# mytracer.net
KiCad netlist of a schematic drawn in EAGLE
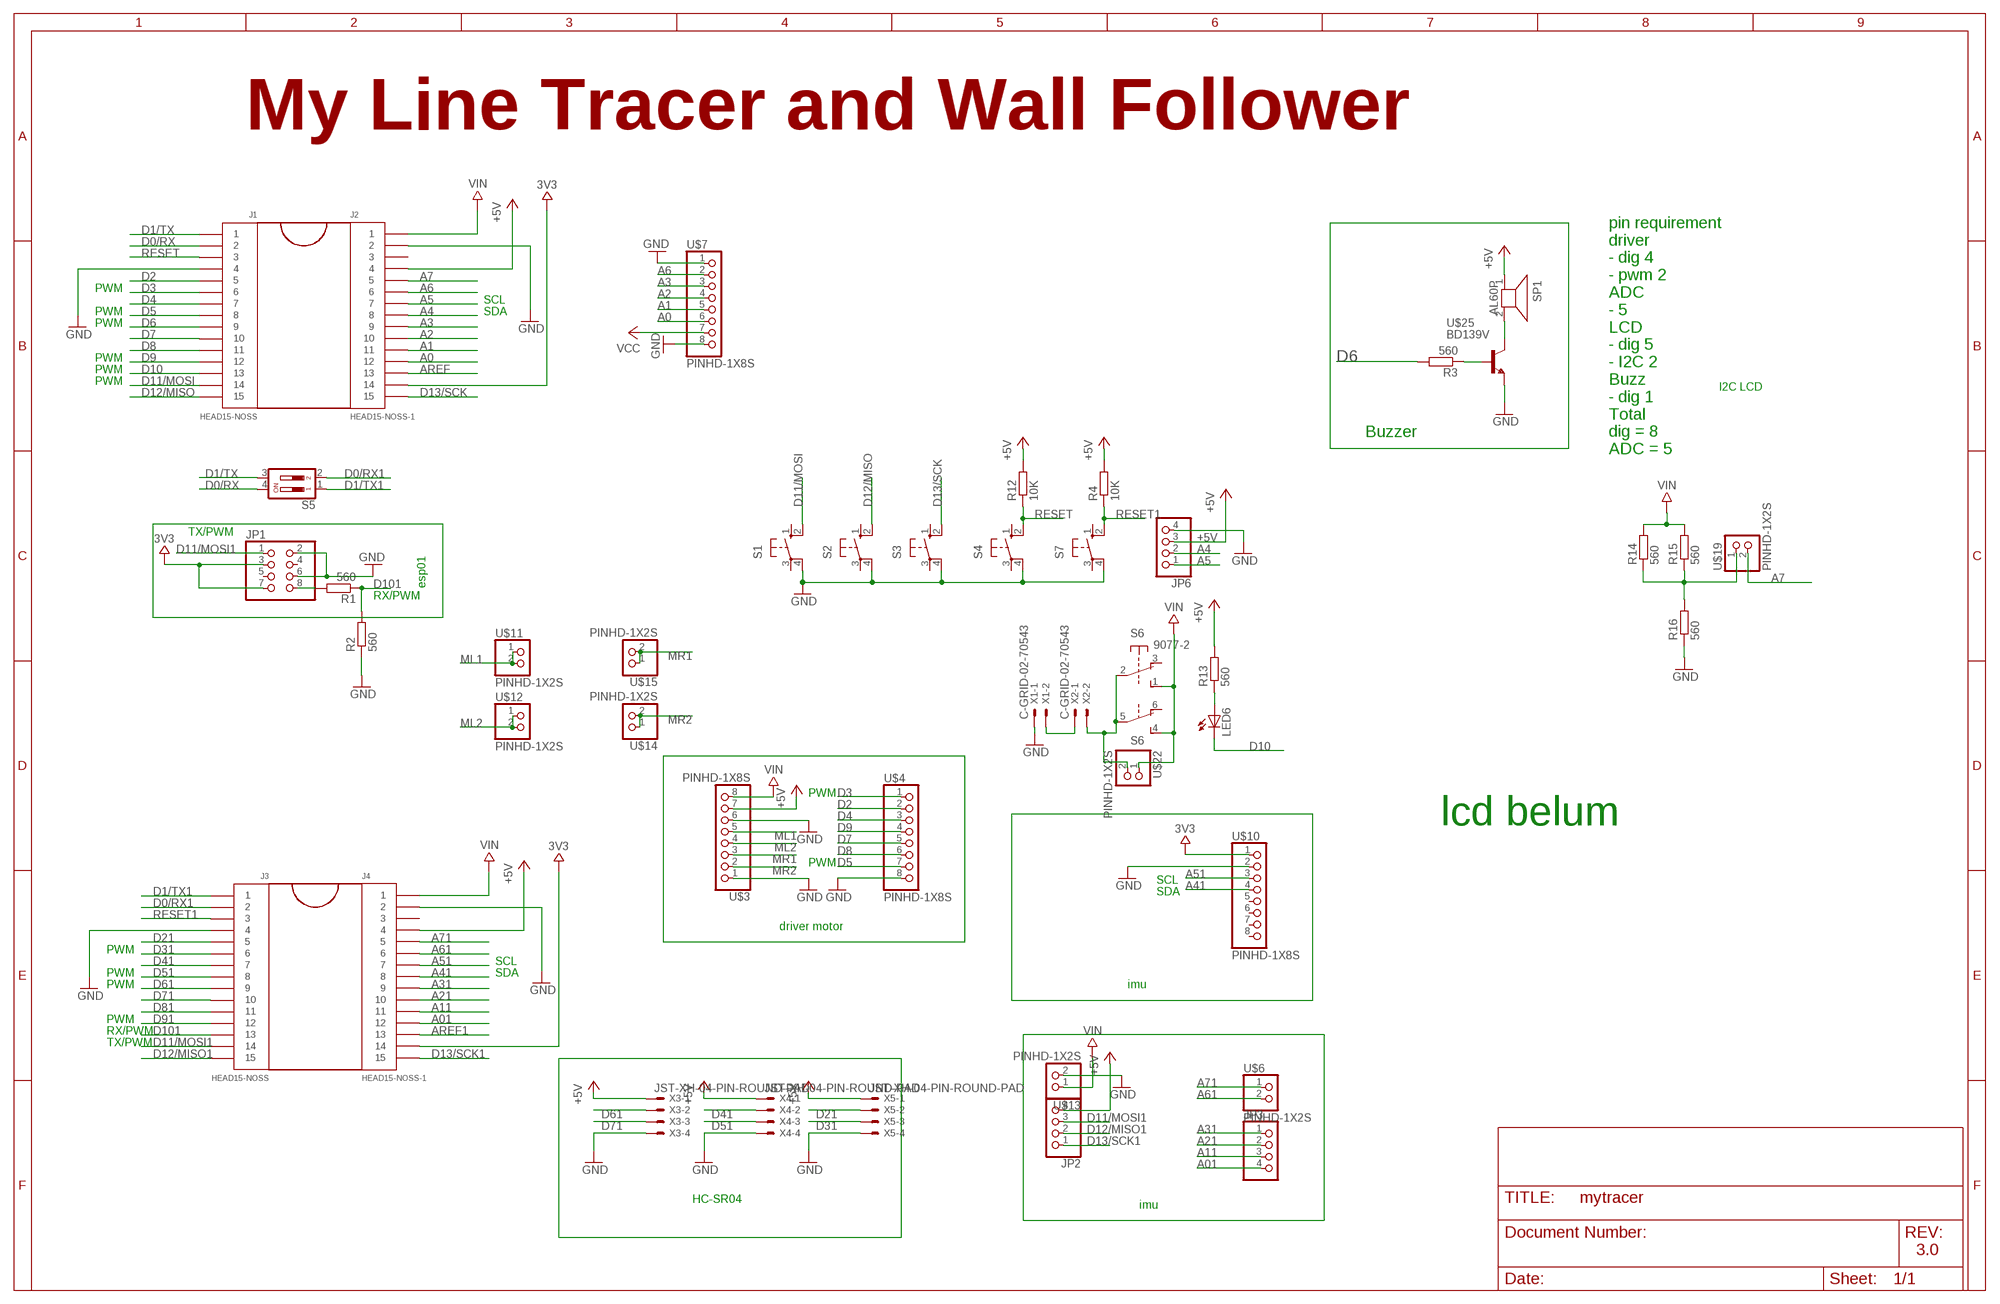
[diagram p0: schematic, sheet 1]

(export (version "E")
  (design (tool "Eeschema 10.0.6"))
  (components
    (comp (ref "J1")
      (value "HEAD15-NOSS")
      (footprint "eagle-import:HEAD15-NOSS")
      (libsource (lib "eagle-import") (part "HEAD15-NOSS"))
    )
    (comp (ref "J2")
      (value "HEAD15-NOSS-1")
      (footprint "eagle-import:HEAD15-NOSS-1")
      (libsource (lib "eagle-import") (part "HEAD15-NOSS-1"))
    )
    (comp (ref "J3")
      (value "HEAD15-NOSS")
      (footprint "eagle-import:HEAD15-NOSS")
      (libsource (lib "eagle-import") (part "HEAD15-NOSS"))
    )
    (comp (ref "J4")
      (value "HEAD15-NOSS-1")
      (footprint "eagle-import:HEAD15-NOSS-1")
      (libsource (lib "eagle-import") (part "HEAD15-NOSS-1"))
    )
    (comp (ref "JP1")
      (value "PINHD-2X4")
      (footprint "eagle-import:2X04")
      (libsource (lib "eagle-import") (part "PINHD-2X4"))
    )
    (comp (ref "JP2")
      (value "PINHD-1X4")
      (footprint "eagle-import:1X04")
      (libsource (lib "eagle-import") (part "PINHD-1X4"))
    )
    (comp (ref "JP3")
      (value "PINHD-1X4")
      (footprint "eagle-import:1X04")
      (libsource (lib "eagle-import") (part "PINHD-1X4"))
    )
    (comp (ref "JP6")
      (value "PINHD-1X4")
      (footprint "eagle-import:1X04")
      (libsource (lib "eagle-import") (part "PINHD-1X4"))
    )
    (comp (ref "LED6")
      (value "LED3MM")
      (footprint "eagle-import:LED3MM")
      (libsource (lib "eagle-import") (part "LED3MM"))
    )
    (comp (ref "R1")
      (value "560")
      (footprint "eagle-import:M1206")
      (libsource (lib "eagle-import") (part "R-EU_M1206"))
    )
    (comp (ref "R2")
      (value "560")
      (footprint "eagle-import:M1206")
      (libsource (lib "eagle-import") (part "R-EU_M1206"))
    )
    (comp (ref "R3")
      (value "560")
      (footprint "eagle-import:M1206")
      (libsource (lib "eagle-import") (part "R-EU_M1206"))
    )
    (comp (ref "R4")
      (value "10K")
      (footprint "eagle-import:M1206")
      (libsource (lib "eagle-import") (part "R-EU_M1206"))
    )
    (comp (ref "R12")
      (value "10K")
      (footprint "eagle-import:M1206")
      (libsource (lib "eagle-import") (part "R-EU_M1206"))
    )
    (comp (ref "R13")
      (value "560")
      (footprint "eagle-import:M1206")
      (libsource (lib "eagle-import") (part "R-EU_M1206"))
    )
    (comp (ref "R14")
      (value "560")
      (footprint "eagle-import:M1206")
      (libsource (lib "eagle-import") (part "R-EU_M1206"))
    )
    (comp (ref "R15")
      (value "560")
      (footprint "eagle-import:M1206")
      (libsource (lib "eagle-import") (part "R-EU_M1206"))
    )
    (comp (ref "R16")
      (value "560")
      (footprint "eagle-import:M1206")
      (libsource (lib "eagle-import") (part "R-EU_M1206"))
    )
    (comp (ref "S1")
      (value "10-XX")
      (footprint "eagle-import:B3F-10XX")
      (fields (field (name "MPN") "B3F-1000"))
      (libsource (lib "eagle-import") (part "10-XX"))
    )
    (comp (ref "S2")
      (value "10-XX")
      (footprint "eagle-import:B3F-10XX")
      (fields (field (name "MPN") "B3F-1000"))
      (libsource (lib "eagle-import") (part "10-XX"))
    )
    (comp (ref "S3")
      (value "10-XX")
      (footprint "eagle-import:B3F-10XX")
      (fields (field (name "MPN") "B3F-1000"))
      (libsource (lib "eagle-import") (part "10-XX"))
    )
    (comp (ref "S4")
      (value "10-XX")
      (footprint "eagle-import:B3F-10XX")
      (fields (field (name "MPN") "B3F-1000"))
      (libsource (lib "eagle-import") (part "10-XX"))
    )
    (comp (ref "S5")
      (value "DIP02YL")
      (footprint "eagle-import:DIP02YL")
      (libsource (lib "eagle-import") (part "DIP02YL"))
    )
    (comp (ref "S6")
      (value "9077-2")
      (footprint "eagle-import:9077-2")
      (libsource (lib "eagle-import") (part "9077-2"))
    )
    (comp (ref "S7")
      (value "10-XX")
      (footprint "eagle-import:B3F-10XX")
      (fields (field (name "MPN") "B3F-1000"))
      (libsource (lib "eagle-import") (part "10-XX"))
    )
    (comp (ref "SP1")
      (value "AL60P")
      (footprint "eagle-import:AL60P")
      (libsource (lib "eagle-import") (part "AL60P"))
    )
    (comp (ref "U$3")
      (value "PINHD-1X8S")
      (footprint "eagle-import:1X08S")
      (libsource (lib "eagle-import") (part "PINHD-1X8S"))
    )
    (comp (ref "U$4")
      (value "PINHD-1X8S")
      (footprint "eagle-import:1X08S")
      (libsource (lib "eagle-import") (part "PINHD-1X8S"))
    )
    (comp (ref "U$6")
      (value "PINHD-1X2S")
      (footprint "eagle-import:1X02S")
      (libsource (lib "eagle-import") (part "PINHD-1X2S"))
    )
    (comp (ref "U$7")
      (value "PINHD-1X8S")
      (footprint "eagle-import:1X08S")
      (libsource (lib "eagle-import") (part "PINHD-1X8S"))
    )
    (comp (ref "U$10")
      (value "PINHD-1X8S")
      (footprint "eagle-import:1X08S")
      (libsource (lib "eagle-import") (part "PINHD-1X8S"))
    )
    (comp (ref "U$11")
      (value "PINHD-1X2S")
      (footprint "eagle-import:1X02S")
      (libsource (lib "eagle-import") (part "PINHD-1X2S"))
    )
    (comp (ref "U$12")
      (value "PINHD-1X2S")
      (footprint "eagle-import:1X02S")
      (libsource (lib "eagle-import") (part "PINHD-1X2S"))
    )
    (comp (ref "U$13")
      (value "PINHD-1X2S")
      (footprint "eagle-import:1X02S")
      (libsource (lib "eagle-import") (part "PINHD-1X2S"))
    )
    (comp (ref "U$14")
      (value "PINHD-1X2S")
      (footprint "eagle-import:1X02S")
      (libsource (lib "eagle-import") (part "PINHD-1X2S"))
    )
    (comp (ref "U$15")
      (value "PINHD-1X2S")
      (footprint "eagle-import:1X02S")
      (libsource (lib "eagle-import") (part "PINHD-1X2S"))
    )
    (comp (ref "U$19")
      (value "PINHD-1X2S")
      (footprint "eagle-import:1X02S")
      (libsource (lib "eagle-import") (part "PINHD-1X2S"))
    )
    (comp (ref "U$22")
      (value "PINHD-1X2S")
      (footprint "eagle-import:1X02S")
      (libsource (lib "eagle-import") (part "PINHD-1X2S"))
    )
    (comp (ref "U$25")
      (value "BD139V")
      (footprint "eagle-import:TO126V")
      (libsource (lib "eagle-import") (part "BD139V"))
    )
    (comp (ref "X1")
      (value "C-GRID-02-70543")
      (footprint "eagle-import:70543-02")
      (libsource (lib "eagle-import") (part "C-GRID-02-70543"))
    )
    (comp (ref "X2")
      (value "C-GRID-02-70543")
      (footprint "eagle-import:70543-02")
      (libsource (lib "eagle-import") (part "C-GRID-02-70543"))
    )
    (comp (ref "X3")
      (value "JST-XH-04-PIN-ROUND-PAD")
      (footprint "eagle-import:JST-XH-04-PACKAGE-ROUND-PAD")
      (libsource (lib "eagle-import") (part "JST-XH-04-PIN-ROUND-PAD"))
    )
    (comp (ref "X4")
      (value "JST-XH-04-PIN-ROUND-PAD")
      (footprint "eagle-import:JST-XH-04-PACKAGE-ROUND-PAD")
      (libsource (lib "eagle-import") (part "JST-XH-04-PIN-ROUND-PAD"))
    )
    (comp (ref "X5")
      (value "JST-XH-04-PIN-ROUND-PAD")
      (footprint "eagle-import:JST-XH-04-PACKAGE-ROUND-PAD")
      (libsource (lib "eagle-import") (part "JST-XH-04-PIN-ROUND-PAD"))
    )
  )
  (nets
    (net (code "1") (name "+5V") (class "Default")
      (node (ref "J2") (pin "4") (pinfunction "4_4") (pintype "passive"))
      (node (ref "J4") (pin "4") (pinfunction "4_4") (pintype "passive"))
      (node (ref "JP2") (pin "4") (pinfunction "4_4") (pintype "passive"))
      (node (ref "JP6") (pin "3") (pinfunction "3_3") (pintype "passive"))
      (node (ref "R12") (pin "2") (pinfunction "2_2") (pintype "passive"))
      (node (ref "R13") (pin "2") (pinfunction "2_2") (pintype "passive"))
      (node (ref "R4") (pin "2") (pinfunction "2_2") (pintype "passive"))
      (node (ref "SP1") (pin "1") (pinfunction "1_1") (pintype "passive"))
      (node (ref "U$3") (pin "7") (pinfunction "7_7") (pintype "passive"))
      (node (ref "X3") (pin "1") (pinfunction "S_1") (pintype "passive"))
      (node (ref "X4") (pin "1") (pinfunction "S_1") (pintype "passive"))
      (node (ref "X5") (pin "1") (pinfunction "S_1") (pintype "passive"))
    )
    (net (code "2") (name "/A0") (class "Default")
      (node (ref "J2") (pin "12") (pinfunction "12_12") (pintype "passive"))
      (node (ref "U$7") (pin "6") (pinfunction "6_6") (pintype "passive"))
    )
    (net (code "3") (name "/A01") (class "Default")
      (node (ref "J4") (pin "12") (pinfunction "12_12") (pintype "passive"))
      (node (ref "JP3") (pin "4") (pinfunction "4_4") (pintype "passive"))
    )
    (net (code "4") (name "/A1") (class "Default")
      (node (ref "J2") (pin "11") (pinfunction "11_11") (pintype "passive"))
      (node (ref "U$7") (pin "5") (pinfunction "5_5") (pintype "passive"))
    )
    (net (code "5") (name "/A2") (class "Default")
      (node (ref "J2") (pin "10") (pinfunction "10_10") (pintype "passive"))
      (node (ref "U$7") (pin "4") (pinfunction "4_4") (pintype "passive"))
    )
    (net (code "6") (name "/A3") (class "Default")
      (node (ref "J2") (pin "9") (pinfunction "9_9") (pintype "passive"))
      (node (ref "U$7") (pin "3") (pinfunction "3_3") (pintype "passive"))
    )
    (net (code "7") (name "/A4") (class "Default")
      (node (ref "J2") (pin "8") (pinfunction "8_8") (pintype "passive"))
      (node (ref "JP6") (pin "2") (pinfunction "2_2") (pintype "passive"))
    )
    (net (code "8") (name "/A5") (class "Default")
      (node (ref "J2") (pin "7") (pinfunction "7_7") (pintype "passive"))
      (node (ref "JP6") (pin "1") (pinfunction "1_1") (pintype "passive"))
    )
    (net (code "9") (name "/A6") (class "Default")
      (node (ref "J2") (pin "6") (pinfunction "6_6") (pintype "passive"))
      (node (ref "U$7") (pin "2") (pinfunction "2_2") (pintype "passive"))
    )
    (net (code "10") (name "/A7") (class "Default")
      (node (ref "J2") (pin "5") (pinfunction "5_5") (pintype "passive"))
      (node (ref "U$19") (pin "2") (pinfunction "2_2") (pintype "passive"))
    )
    (net (code "11") (name "/A11") (class "Default")
      (node (ref "J4") (pin "11") (pinfunction "11_11") (pintype "passive"))
      (node (ref "JP3") (pin "3") (pinfunction "3_3") (pintype "passive"))
    )
    (net (code "12") (name "/A21") (class "Default")
      (node (ref "J4") (pin "10") (pinfunction "10_10") (pintype "passive"))
      (node (ref "JP3") (pin "2") (pinfunction "2_2") (pintype "passive"))
    )
    (net (code "13") (name "/A31") (class "Default")
      (node (ref "J4") (pin "9") (pinfunction "9_9") (pintype "passive"))
      (node (ref "JP3") (pin "1") (pinfunction "1_1") (pintype "passive"))
    )
    (net (code "14") (name "/A41") (class "Default")
      (node (ref "J4") (pin "8") (pinfunction "8_8") (pintype "passive"))
      (node (ref "U$10") (pin "4") (pinfunction "4_4") (pintype "passive"))
    )
    (net (code "15") (name "/A51") (class "Default")
      (node (ref "J4") (pin "7") (pinfunction "7_7") (pintype "passive"))
      (node (ref "U$10") (pin "3") (pinfunction "3_3") (pintype "passive"))
    )
    (net (code "16") (name "/A61") (class "Default")
      (node (ref "J4") (pin "6") (pinfunction "6_6") (pintype "passive"))
      (node (ref "U$6") (pin "2") (pinfunction "2_2") (pintype "passive"))
    )
    (net (code "17") (name "/A71") (class "Default")
      (node (ref "J4") (pin "5") (pinfunction "5_5") (pintype "passive"))
      (node (ref "U$6") (pin "1") (pinfunction "1_1") (pintype "passive"))
    )
    (net (code "18") (name "/AREF") (class "Default")
      (node (ref "J2") (pin "13") (pinfunction "13_13") (pintype "passive"))
    )
    (net (code "19") (name "/AREF1") (class "Default")
      (node (ref "J4") (pin "13") (pinfunction "13_13") (pintype "passive"))
    )
    (net (code "20") (name "/D0{slash}RX") (class "Default")
      (node (ref "J1") (pin "2") (pinfunction "2_2") (pintype "passive"))
      (node (ref "S5") (pin "4") (pinfunction "4_4") (pintype "passive"))
    )
    (net (code "21") (name "/D0{slash}RX1") (class "Default")
      (node (ref "J3") (pin "2") (pinfunction "2_2") (pintype "passive"))
      (node (ref "S5") (pin "2") (pinfunction "2_2") (pintype "passive"))
    )
    (net (code "22") (name "/D1{slash}TX") (class "Default")
      (node (ref "J1") (pin "1") (pinfunction "1_1") (pintype "passive"))
      (node (ref "S5") (pin "3") (pinfunction "3_3") (pintype "passive"))
    )
    (net (code "23") (name "/D1{slash}TX1") (class "Default")
      (node (ref "J3") (pin "1") (pinfunction "1_1") (pintype "passive"))
      (node (ref "S5") (pin "1") (pinfunction "1_1") (pintype "passive"))
    )
    (net (code "24") (name "/D2") (class "Default")
      (node (ref "J1") (pin "5") (pinfunction "5_5") (pintype "passive"))
      (node (ref "U$4") (pin "2") (pinfunction "2_2") (pintype "passive"))
    )
    (net (code "25") (name "/D3") (class "Default")
      (node (ref "J1") (pin "6") (pinfunction "6_6") (pintype "passive"))
      (node (ref "U$4") (pin "1") (pinfunction "1_1") (pintype "passive"))
    )
    (net (code "26") (name "/D4") (class "Default")
      (node (ref "J1") (pin "7") (pinfunction "7_7") (pintype "passive"))
      (node (ref "U$4") (pin "3") (pinfunction "3_3") (pintype "passive"))
    )
    (net (code "27") (name "/D5") (class "Default")
      (node (ref "J1") (pin "8") (pinfunction "8_8") (pintype "passive"))
      (node (ref "U$4") (pin "7") (pinfunction "7_7") (pintype "passive"))
    )
    (net (code "28") (name "/D6") (class "Default")
      (node (ref "J1") (pin "9") (pinfunction "9_9") (pintype "passive"))
      (node (ref "R3") (pin "2") (pinfunction "2_2") (pintype "passive"))
    )
    (net (code "29") (name "/D7") (class "Default")
      (node (ref "J1") (pin "10") (pinfunction "10_10") (pintype "passive"))
      (node (ref "U$4") (pin "5") (pinfunction "5_5") (pintype "passive"))
    )
    (net (code "30") (name "/D8") (class "Default")
      (node (ref "J1") (pin "11") (pinfunction "11_11") (pintype "passive"))
      (node (ref "U$4") (pin "6") (pinfunction "6_6") (pintype "passive"))
    )
    (net (code "31") (name "/D9") (class "Default")
      (node (ref "J1") (pin "12") (pinfunction "12_12") (pintype "passive"))
      (node (ref "U$4") (pin "4") (pinfunction "4_4") (pintype "passive"))
    )
    (net (code "32") (name "/D10") (class "Default")
      (node (ref "J1") (pin "13") (pinfunction "13_13") (pintype "passive"))
      (node (ref "LED6") (pin "K") (pinfunction "C_K") (pintype "passive"))
    )
    (net (code "33") (name "/D11{slash}MOSI") (class "Default")
      (node (ref "J1") (pin "14") (pinfunction "14_14") (pintype "passive"))
      (node (ref "S1") (pin "2") (pinfunction "S1_2") (pintype "passive"))
    )
    (net (code "34") (name "/D11{slash}MOSI1") (class "Default")
      (node (ref "J3") (pin "14") (pinfunction "14_14") (pintype "passive"))
      (node (ref "JP1") (pin "1") (pinfunction "1_1") (pintype "passive"))
      (node (ref "JP2") (pin "3") (pinfunction "3_3") (pintype "passive"))
    )
    (net (code "35") (name "/D12{slash}MISO") (class "Default")
      (node (ref "J1") (pin "15") (pinfunction "15_15") (pintype "passive"))
      (node (ref "S2") (pin "2") (pinfunction "S1_2") (pintype "passive"))
    )
    (net (code "36") (name "/D12{slash}MISO1") (class "Default")
      (node (ref "J3") (pin "15") (pinfunction "15_15") (pintype "passive"))
      (node (ref "JP2") (pin "2") (pinfunction "2_2") (pintype "passive"))
    )
    (net (code "37") (name "/D13{slash}SCK") (class "Default")
      (node (ref "J2") (pin "15") (pinfunction "15_15") (pintype "passive"))
      (node (ref "S3") (pin "2") (pinfunction "S1_2") (pintype "passive"))
    )
    (net (code "38") (name "/D13{slash}SCK1") (class "Default")
      (node (ref "J4") (pin "15") (pinfunction "15_15") (pintype "passive"))
      (node (ref "JP2") (pin "1") (pinfunction "1_1") (pintype "passive"))
    )
    (net (code "39") (name "/D21") (class "Default")
      (node (ref "J3") (pin "5") (pinfunction "5_5") (pintype "passive"))
      (node (ref "X5") (pin "2") (pinfunction "S_2") (pintype "passive"))
    )
    (net (code "40") (name "/D31") (class "Default")
      (node (ref "J3") (pin "6") (pinfunction "6_6") (pintype "passive"))
      (node (ref "X5") (pin "3") (pinfunction "S_3") (pintype "passive"))
    )
    (net (code "41") (name "/D41") (class "Default")
      (node (ref "J3") (pin "7") (pinfunction "7_7") (pintype "passive"))
      (node (ref "X4") (pin "2") (pinfunction "S_2") (pintype "passive"))
    )
    (net (code "42") (name "/D51") (class "Default")
      (node (ref "J3") (pin "8") (pinfunction "8_8") (pintype "passive"))
      (node (ref "X4") (pin "3") (pinfunction "S_3") (pintype "passive"))
    )
    (net (code "43") (name "/D61") (class "Default")
      (node (ref "J3") (pin "9") (pinfunction "9_9") (pintype "passive"))
      (node (ref "X3") (pin "2") (pinfunction "S_2") (pintype "passive"))
    )
    (net (code "44") (name "/D71") (class "Default")
      (node (ref "J3") (pin "10") (pinfunction "10_10") (pintype "passive"))
      (node (ref "X3") (pin "3") (pinfunction "S_3") (pintype "passive"))
    )
    (net (code "45") (name "/D81") (class "Default")
      (node (ref "J3") (pin "11") (pinfunction "11_11") (pintype "passive"))
    )
    (net (code "46") (name "/D91") (class "Default")
      (node (ref "J3") (pin "12") (pinfunction "12_12") (pintype "passive"))
    )
    (net (code "47") (name "/D101") (class "Default")
      (node (ref "J3") (pin "13") (pinfunction "13_13") (pintype "passive"))
      (node (ref "R1") (pin "1") (pinfunction "1_1") (pintype "passive"))
      (node (ref "R2") (pin "2") (pinfunction "2_2") (pintype "passive"))
    )
    (net (code "48") (name "/ML1") (class "Default")
      (node (ref "U$11") (pin "1") (pinfunction "1_1") (pintype "passive"))
      (node (ref "U$11") (pin "2") (pinfunction "2_2") (pintype "passive"))
      (node (ref "U$3") (pin "5") (pinfunction "5_5") (pintype "passive"))
    )
    (net (code "49") (name "/ML2") (class "Default")
      (node (ref "U$12") (pin "1") (pinfunction "1_1") (pintype "passive"))
      (node (ref "U$12") (pin "2") (pinfunction "2_2") (pintype "passive"))
      (node (ref "U$3") (pin "4") (pinfunction "4_4") (pintype "passive"))
    )
    (net (code "50") (name "/MR1") (class "Default")
      (node (ref "U$15") (pin "1") (pinfunction "1_1") (pintype "passive"))
      (node (ref "U$15") (pin "2") (pinfunction "2_2") (pintype "passive"))
      (node (ref "U$3") (pin "3") (pinfunction "3_3") (pintype "passive"))
    )
    (net (code "51") (name "/MR2") (class "Default")
      (node (ref "U$14") (pin "1") (pinfunction "1_1") (pintype "passive"))
      (node (ref "U$14") (pin "2") (pinfunction "2_2") (pintype "passive"))
      (node (ref "U$3") (pin "2") (pinfunction "2_2") (pintype "passive"))
    )
    (net (code "52") (name "/RESET") (class "Default")
      (node (ref "J1") (pin "3") (pinfunction "3_3") (pintype "passive"))
      (node (ref "R12") (pin "1") (pinfunction "1_1") (pintype "passive"))
      (node (ref "S4") (pin "2") (pinfunction "S1_2") (pintype "passive"))
    )
    (net (code "53") (name "/RESET1") (class "Default")
      (node (ref "J3") (pin "3") (pinfunction "3_3") (pintype "passive"))
      (node (ref "R4") (pin "1") (pinfunction "1_1") (pintype "passive"))
      (node (ref "S7") (pin "2") (pinfunction "S1_2") (pintype "passive"))
    )
    (net (code "54") (name "3V3") (class "Default")
      (node (ref "J2") (pin "14") (pinfunction "14_14") (pintype "passive"))
      (node (ref "J4") (pin "14") (pinfunction "14_14") (pintype "passive"))
      (node (ref "JP1") (pin "3") (pinfunction "3_3") (pintype "passive"))
      (node (ref "JP1") (pin "7") (pinfunction "7_7") (pintype "passive"))
      (node (ref "U$10") (pin "1") (pinfunction "1_1") (pintype "passive"))
    )
    (net (code "55") (name "GND") (class "Default")
      (node (ref "J1") (pin "4") (pinfunction "4_4") (pintype "passive"))
      (node (ref "J2") (pin "2") (pinfunction "2_2") (pintype "passive"))
      (node (ref "J3") (pin "4") (pinfunction "4_4") (pintype "passive"))
      (node (ref "J4") (pin "2") (pinfunction "2_2") (pintype "passive"))
      (node (ref "JP1") (pin "2") (pinfunction "2_2") (pintype "passive"))
      (node (ref "JP1") (pin "6") (pinfunction "6_6") (pintype "passive"))
      (node (ref "JP6") (pin "4") (pinfunction "4_4") (pintype "passive"))
      (node (ref "R16") (pin "1") (pinfunction "1_1") (pintype "passive"))
      (node (ref "R2") (pin "1") (pinfunction "1_1") (pintype "passive"))
      (node (ref "S1") (pin "4") (pinfunction "P1_4") (pintype "passive"))
      (node (ref "S2") (pin "4") (pinfunction "P1_4") (pintype "passive"))
      (node (ref "S3") (pin "4") (pinfunction "P1_4") (pintype "passive"))
      (node (ref "S4") (pin "4") (pinfunction "P1_4") (pintype "passive"))
      (node (ref "S7") (pin "4") (pinfunction "P1_4") (pintype "passive"))
      (node (ref "U$10") (pin "2") (pinfunction "2_2") (pintype "passive"))
      (node (ref "U$13") (pin "2") (pinfunction "2_2") (pintype "passive"))
      (node (ref "U$25") (pin "1") (pinfunction "E_1") (pintype "passive"))
      (node (ref "U$3") (pin "1") (pinfunction "1_1") (pintype "passive"))
      (node (ref "U$3") (pin "6") (pinfunction "6_6") (pintype "passive"))
      (node (ref "U$4") (pin "8") (pinfunction "8_8") (pintype "passive"))
      (node (ref "U$7") (pin "1") (pinfunction "1_1") (pintype "passive"))
      (node (ref "U$7") (pin "8") (pinfunction "8_8") (pintype "passive"))
      (node (ref "X1") (pin "1") (pinfunction "S_1") (pintype "passive"))
      (node (ref "X3") (pin "4") (pinfunction "S_4") (pintype "passive"))
      (node (ref "X4") (pin "4") (pinfunction "S_4") (pintype "passive"))
      (node (ref "X5") (pin "4") (pinfunction "S_4") (pintype "passive"))
    )
    (net (code "56") (name "Net-(JP1-Pad8)") (class "Default")
      (node (ref "JP1") (pin "8") (pinfunction "8_8") (pintype "passive"))
      (node (ref "R1") (pin "2") (pinfunction "2_2") (pintype "passive"))
    )
    (net (code "57") (name "Net-(LED6-PadA)") (class "Default")
      (node (ref "LED6") (pin "A") (pinfunction "A_A") (pintype "passive"))
      (node (ref "R13") (pin "1") (pinfunction "1_1") (pintype "passive"))
    )
    (net (code "58") (name "Net-(R14-Pad1)") (class "Default")
      (node (ref "R14") (pin "1") (pinfunction "1_1") (pintype "passive"))
      (node (ref "R15") (pin "1") (pinfunction "1_1") (pintype "passive"))
      (node (ref "R16") (pin "2") (pinfunction "2_2") (pintype "passive"))
      (node (ref "U$19") (pin "1") (pinfunction "1_1") (pintype "passive"))
    )
    (net (code "59") (name "Net-(S6A-P)") (class "Default")
      (node (ref "S6") (pin "2") (pinfunction "P_2") (pintype "passive"))
      (node (ref "S6") (pin "5") (pinfunction "P_5") (pintype "passive"))
      (node (ref "U$22") (pin "2") (pinfunction "2_2") (pintype "passive"))
      (node (ref "X2") (pin "2") (pinfunction "S_2") (pintype "passive"))
    )
    (net (code "60") (name "Net-(U$25-B)") (class "Default")
      (node (ref "R3") (pin "1") (pinfunction "1_1") (pintype "passive"))
      (node (ref "U$25") (pin "3") (pinfunction "B_3") (pintype "passive"))
    )
    (net (code "61") (name "Net-(U$25-C)") (class "Default")
      (node (ref "SP1") (pin "2") (pinfunction "2_2") (pintype "passive"))
      (node (ref "U$25") (pin "2") (pinfunction "C_2") (pintype "passive"))
    )
    (net (code "62") (name "Net-(X1B-S)") (class "Default")
      (node (ref "X1") (pin "2") (pinfunction "S_2") (pintype "passive"))
      (node (ref "X2") (pin "1") (pinfunction "S_1") (pintype "passive"))
    )
    (net (code "63") (name "VCC") (class "Default")
      (node (ref "U$7") (pin "7") (pinfunction "7_7") (pintype "passive"))
    )
    (net (code "64") (name "VIN") (class "Default")
      (node (ref "J2") (pin "1") (pinfunction "1_1") (pintype "passive"))
      (node (ref "J4") (pin "1") (pinfunction "1_1") (pintype "passive"))
      (node (ref "R14") (pin "2") (pinfunction "2_2") (pintype "passive"))
      (node (ref "R15") (pin "2") (pinfunction "2_2") (pintype "passive"))
      (node (ref "S6") (pin "1") (pinfunction "S_1") (pintype "passive"))
      (node (ref "S6") (pin "4") (pinfunction "S_4") (pintype "passive"))
      (node (ref "U$13") (pin "1") (pinfunction "1_1") (pintype "passive"))
      (node (ref "U$22") (pin "1") (pinfunction "1_1") (pintype "passive"))
      (node (ref "U$3") (pin "8") (pinfunction "8_8") (pintype "passive"))
    )
    (net (code "65") (name "unconnected-(J2-Pad3)") (class "Default")
      (node (ref "J2") (pin "3") (pinfunction "3_3") (pintype "passive"))
    )
    (net (code "66") (name "unconnected-(J4-Pad3)") (class "Default")
      (node (ref "J4") (pin "3") (pinfunction "3_3") (pintype "passive"))
    )
    (net (code "67") (name "unconnected-(JP1-Pad4)") (class "Default")
      (node (ref "JP1") (pin "4") (pinfunction "4_4") (pintype "passive"))
    )
    (net (code "68") (name "unconnected-(JP1-Pad5)") (class "Default")
      (node (ref "JP1") (pin "5") (pinfunction "5_5") (pintype "passive"))
    )
    (net (code "69") (name "unconnected-(S1-P-Pad3)") (class "Default")
      (node (ref "S1") (pin "3") (pinfunction "P_3") (pintype "passive"))
    )
    (net (code "70") (name "unconnected-(S1-S-Pad1)") (class "Default")
      (node (ref "S1") (pin "1") (pinfunction "S_1") (pintype "passive"))
    )
    (net (code "71") (name "unconnected-(S2-P-Pad3)") (class "Default")
      (node (ref "S2") (pin "3") (pinfunction "P_3") (pintype "passive"))
    )
    (net (code "72") (name "unconnected-(S2-S-Pad1)") (class "Default")
      (node (ref "S2") (pin "1") (pinfunction "S_1") (pintype "passive"))
    )
    (net (code "73") (name "unconnected-(S3-P-Pad3)") (class "Default")
      (node (ref "S3") (pin "3") (pinfunction "P_3") (pintype "passive"))
    )
    (net (code "74") (name "unconnected-(S3-S-Pad1)") (class "Default")
      (node (ref "S3") (pin "1") (pinfunction "S_1") (pintype "passive"))
    )
    (net (code "75") (name "unconnected-(S4-P-Pad3)") (class "Default")
      (node (ref "S4") (pin "3") (pinfunction "P_3") (pintype "passive"))
    )
    (net (code "76") (name "unconnected-(S4-S-Pad1)") (class "Default")
      (node (ref "S4") (pin "1") (pinfunction "S_1") (pintype "passive"))
    )
    (net (code "77") (name "unconnected-(S6A-O-Pad3)") (class "Default")
      (node (ref "S6") (pin "3") (pinfunction "O_3") (pintype "passive"))
    )
    (net (code "78") (name "unconnected-(S6B-O-Pad6)") (class "Default")
      (node (ref "S6") (pin "6") (pinfunction "O_6") (pintype "passive"))
    )
    (net (code "79") (name "unconnected-(S7-P-Pad3)") (class "Default")
      (node (ref "S7") (pin "3") (pinfunction "P_3") (pintype "passive"))
    )
    (net (code "80") (name "unconnected-(S7-S-Pad1)") (class "Default")
      (node (ref "S7") (pin "1") (pinfunction "S_1") (pintype "passive"))
    )
    (net (code "81") (name "unconnected-(U$10-Pad5)") (class "Default")
      (node (ref "U$10") (pin "5") (pinfunction "5_5") (pintype "passive"))
    )
    (net (code "82") (name "unconnected-(U$10-Pad6)") (class "Default")
      (node (ref "U$10") (pin "6") (pinfunction "6_6") (pintype "passive"))
    )
    (net (code "83") (name "unconnected-(U$10-Pad7)") (class "Default")
      (node (ref "U$10") (pin "7") (pinfunction "7_7") (pintype "passive"))
    )
    (net (code "84") (name "unconnected-(U$10-Pad8)") (class "Default")
      (node (ref "U$10") (pin "8") (pinfunction "8_8") (pintype "passive"))
    )
  )
)
